# Renesas_Raspi2_Add_On_V1.net
KiCad netlist of a schematic drawn in EAGLE
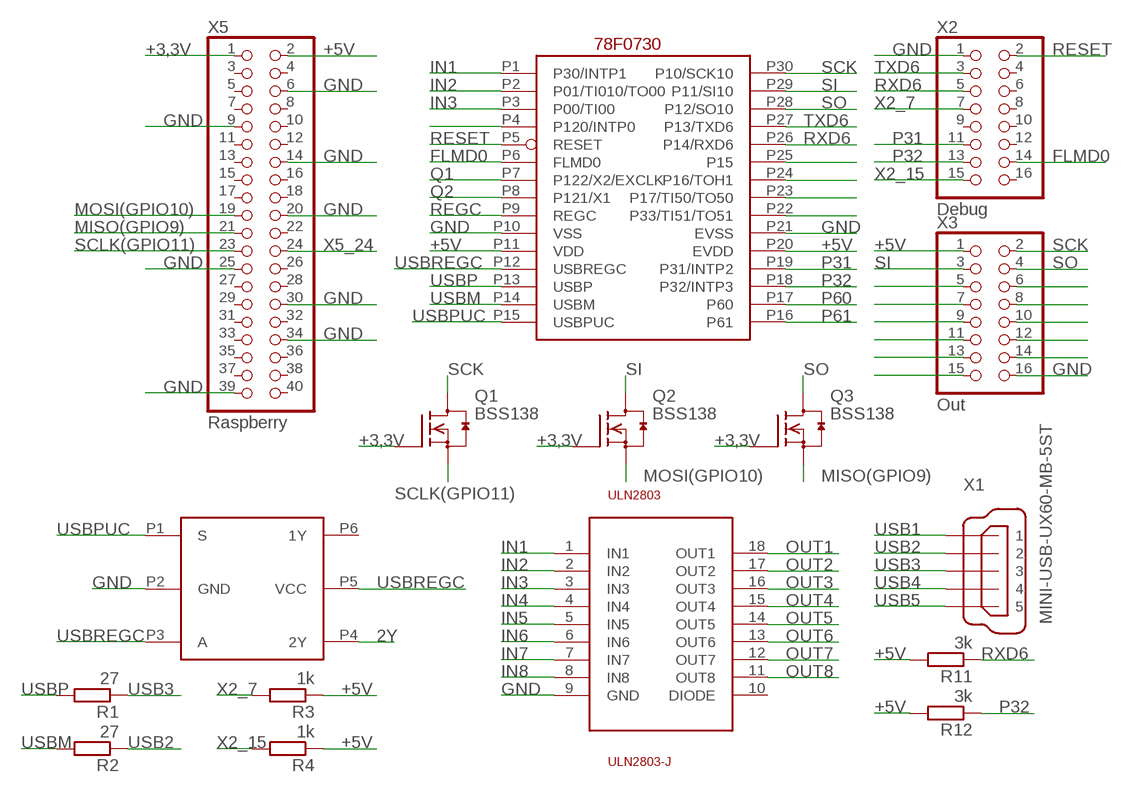
[diagram p0: schematic, sheet 1]
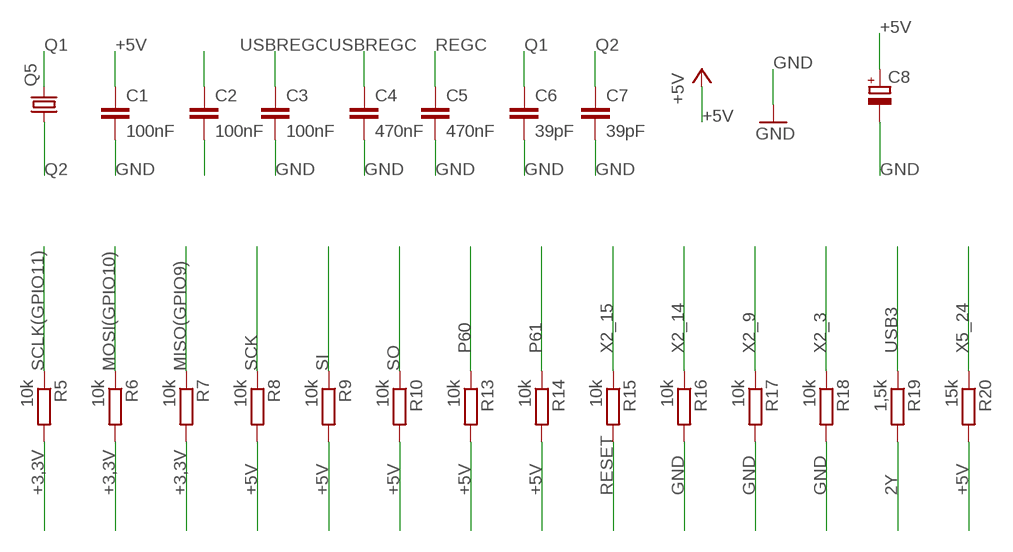
[diagram p1: schematic, sheet 2]

(export (version "E")
  (design (tool "Eeschema 10.0.6"))
  (components
    (comp (ref "Q1")
      (value "BSS138")
      (footprint "eagle-import:SOT23")
      (libsource (lib "eagle-import") (part "BSS138"))
    )
    (comp (ref "Q2")
      (value "BSS138")
      (footprint "eagle-import:SOT23")
      (libsource (lib "eagle-import") (part "BSS138"))
    )
    (comp (ref "Q3")
      (value "BSS138")
      (footprint "eagle-import:SOT23")
      (libsource (lib "eagle-import") (part "BSS138"))
    )
    (comp (ref "R1")
      (value "27")
      (footprint "eagle-import:R0603")
      (libsource (lib "eagle-import") (part "R-EU_R0603"))
    )
    (comp (ref "R2")
      (value "27")
      (footprint "eagle-import:R0603")
      (libsource (lib "eagle-import") (part "R-EU_R0603"))
    )
    (comp (ref "R3")
      (value "1k")
      (footprint "eagle-import:R0603")
      (libsource (lib "eagle-import") (part "R-EU_R0603"))
    )
    (comp (ref "R4")
      (value "1k")
      (footprint "eagle-import:R0603")
      (libsource (lib "eagle-import") (part "R-EU_R0603"))
    )
    (comp (ref "R11")
      (value "3k")
      (footprint "eagle-import:R0603")
      (libsource (lib "eagle-import") (part "R-EU_R0603"))
    )
    (comp (ref "R12")
      (value "3k")
      (footprint "eagle-import:R0603")
      (libsource (lib "eagle-import") (part "R-EU_R0603"))
    )
    (comp (ref "U$1")
      (value "78F0730_CAB_AX")
      (footprint "eagle-import:SSOP30")
      (libsource (lib "eagle-import") (part "78F0730_CAB_AX"))
    )
    (comp (ref "U$2")
      (value "74LVC1G18")
      (footprint "eagle-import:74LVC1G18")
      (libsource (lib "eagle-import") (part "74LVC1G18"))
    )
    (comp (ref "ULN2803")
      (value "ULN2803-J")
      (footprint "eagle-import:SOJ18-45")
      (libsource (lib "eagle-import") (part "ULN2803-J"))
    )
    (comp (ref "X1")
      (value "MINI-USB-UX60-MB-5ST")
      (footprint "eagle-import:UX60-MB-5ST")
      (libsource (lib "eagle-import") (part "MINI-USB-UX60-MB-5ST"))
    )
    (comp (ref "X2")
      (value "Debug")
      (footprint "eagle-import:2X08")
      (libsource (lib "eagle-import") (part "PINHD-2X8"))
    )
    (comp (ref "X3")
      (value "Out")
      (footprint "eagle-import:2X08")
      (libsource (lib "eagle-import") (part "PINHD-2X8"))
    )
    (comp (ref "X5")
      (value "Raspberry")
      (footprint "eagle-import:2X20")
      (libsource (lib "eagle-import") (part "PINHD-2X20"))
    )
    (comp (ref "C1")
      (value "100nF")
      (footprint "eagle-import:C0603")
      (libsource (lib "eagle-import") (part "C-EUC0603"))
    )
    (comp (ref "C2")
      (value "100nF")
      (footprint "eagle-import:C0603")
      (libsource (lib "eagle-import") (part "C-EUC0603"))
    )
    (comp (ref "C3")
      (value "100nF")
      (footprint "eagle-import:C0603")
      (libsource (lib "eagle-import") (part "C-EUC0603"))
    )
    (comp (ref "C4")
      (value "470nF")
      (footprint "eagle-import:C0603")
      (libsource (lib "eagle-import") (part "C-EUC0603"))
    )
    (comp (ref "C5")
      (value "470nF")
      (footprint "eagle-import:C0603")
      (libsource (lib "eagle-import") (part "C-EUC0603"))
    )
    (comp (ref "C6")
      (value "39pF")
      (footprint "eagle-import:C0603")
      (libsource (lib "eagle-import") (part "C-EUC0603"))
    )
    (comp (ref "C7")
      (value "39pF")
      (footprint "eagle-import:C0603")
      (libsource (lib "eagle-import") (part "C-EUC0603"))
    )
    (comp (ref "C8")
      (value "CPOL-EUSANYO_SMD_F8")
      (footprint "eagle-import:SANYO-OSCON_SMD_F8")
      (libsource (lib "eagle-import") (part "CPOL-EUSANYO_SMD_F8"))
    )
    (comp (ref "Q5")
      (value "CRYSTALHC49UP")
      (footprint "eagle-import:HC49UP")
      (libsource (lib "eagle-import") (part "CRYSTALHC49UP"))
    )
    (comp (ref "R5")
      (value "10k")
      (footprint "eagle-import:R0603")
      (libsource (lib "eagle-import") (part "R-EU_R0603"))
    )
    (comp (ref "R6")
      (value "10k")
      (footprint "eagle-import:R0603")
      (libsource (lib "eagle-import") (part "R-EU_R0603"))
    )
    (comp (ref "R7")
      (value "10k")
      (footprint "eagle-import:R0603")
      (libsource (lib "eagle-import") (part "R-EU_R0603"))
    )
    (comp (ref "R8")
      (value "10k")
      (footprint "eagle-import:R0603")
      (libsource (lib "eagle-import") (part "R-EU_R0603"))
    )
    (comp (ref "R9")
      (value "10k")
      (footprint "eagle-import:R0603")
      (libsource (lib "eagle-import") (part "R-EU_R0603"))
    )
    (comp (ref "R10")
      (value "10k")
      (footprint "eagle-import:R0603")
      (libsource (lib "eagle-import") (part "R-EU_R0603"))
    )
    (comp (ref "R13")
      (value "10k")
      (footprint "eagle-import:R0603")
      (libsource (lib "eagle-import") (part "R-EU_R0603"))
    )
    (comp (ref "R14")
      (value "10k")
      (footprint "eagle-import:R0603")
      (libsource (lib "eagle-import") (part "R-EU_R0603"))
    )
    (comp (ref "R15")
      (value "10k")
      (footprint "eagle-import:R0603")
      (libsource (lib "eagle-import") (part "R-EU_R0603"))
    )
    (comp (ref "R16")
      (value "10k")
      (footprint "eagle-import:R0603")
      (libsource (lib "eagle-import") (part "R-EU_R0603"))
    )
    (comp (ref "R17")
      (value "10k")
      (footprint "eagle-import:R0603")
      (libsource (lib "eagle-import") (part "R-EU_R0603"))
    )
    (comp (ref "R18")
      (value "10k")
      (footprint "eagle-import:R0603")
      (libsource (lib "eagle-import") (part "R-EU_R0603"))
    )
    (comp (ref "R19")
      (value "1,5k")
      (footprint "eagle-import:R0603")
      (libsource (lib "eagle-import") (part "R-EU_R0603"))
    )
    (comp (ref "R20")
      (value "15k")
      (footprint "eagle-import:R0603")
      (libsource (lib "eagle-import") (part "R-EU_R0603"))
    )
  )
  (nets
    (net (code "1") (name "+3,3V") (class "Default")
      (node (ref "Q1") (pin "1") (pinfunction "G_1") (pintype "passive"))
      (node (ref "Q2") (pin "1") (pinfunction "G_1") (pintype "passive"))
      (node (ref "Q3") (pin "1") (pinfunction "G_1") (pintype "passive"))
      (node (ref "R5") (pin "2") (pinfunction "2_2") (pintype "passive"))
      (node (ref "R6") (pin "2") (pinfunction "2_2") (pintype "passive"))
      (node (ref "R7") (pin "2") (pinfunction "2_2") (pintype "passive"))
      (node (ref "X5") (pin "1") (pinfunction "1_1") (pintype "passive"))
    )
    (net (code "2") (name "+5V") (class "Default")
      (node (ref "C1") (pin "1") (pinfunction "1_1") (pintype "passive"))
      (node (ref "C8") (pin "+") (pinfunction "+_+") (pintype "passive"))
      (node (ref "R10") (pin "2") (pinfunction "2_2") (pintype "passive"))
      (node (ref "R11") (pin "2") (pinfunction "2_2") (pintype "passive"))
      (node (ref "R12") (pin "2") (pinfunction "2_2") (pintype "passive"))
      (node (ref "R13") (pin "2") (pinfunction "2_2") (pintype "passive"))
      (node (ref "R14") (pin "2") (pinfunction "2_2") (pintype "passive"))
      (node (ref "R20") (pin "2") (pinfunction "2_2") (pintype "passive"))
      (node (ref "R3") (pin "1") (pinfunction "1_1") (pintype "passive"))
      (node (ref "R4") (pin "1") (pinfunction "1_1") (pintype "passive"))
      (node (ref "R8") (pin "2") (pinfunction "2_2") (pintype "passive"))
      (node (ref "R9") (pin "2") (pinfunction "2_2") (pintype "passive"))
      (node (ref "U$1") (pin "P11") (pinfunction "VDD_P11") (pintype "bidirectional"))
      (node (ref "U$1") (pin "P20") (pinfunction "EVDD_P20") (pintype "bidirectional"))
      (node (ref "X3") (pin "1") (pinfunction "1_1") (pintype "passive"))
      (node (ref "X5") (pin "2") (pinfunction "2_2") (pintype "passive"))
    )
    (net (code "3") (name "2Y") (class "Default")
      (node (ref "R19") (pin "2") (pinfunction "2_2") (pintype "passive"))
      (node (ref "U$2") (pin "P4") (pinfunction "2Y_P4") (pintype "bidirectional"))
    )
    (net (code "4") (name "DIODE") (class "Default")
      (node (ref "ULN2803") (pin "10") (pinfunction "DIODE_10") (pintype "power_in"))
    )
    (net (code "5") (name "FLMD0") (class "Default")
      (node (ref "U$1") (pin "P6") (pinfunction "FLMD0_P6") (pintype "bidirectional"))
      (node (ref "X2") (pin "14") (pinfunction "14_14") (pintype "passive"))
    )
    (net (code "6") (name "GND") (class "Default")
      (node (ref "C1") (pin "2") (pinfunction "2_2") (pintype "passive"))
      (node (ref "C3") (pin "2") (pinfunction "2_2") (pintype "passive"))
      (node (ref "C4") (pin "2") (pinfunction "2_2") (pintype "passive"))
      (node (ref "C5") (pin "2") (pinfunction "2_2") (pintype "passive"))
      (node (ref "C6") (pin "2") (pinfunction "2_2") (pintype "passive"))
      (node (ref "C7") (pin "2") (pinfunction "2_2") (pintype "passive"))
      (node (ref "C8") (pin "-") (pinfunction "-_-") (pintype "passive"))
      (node (ref "R16") (pin "2") (pinfunction "2_2") (pintype "passive"))
      (node (ref "R17") (pin "2") (pinfunction "2_2") (pintype "passive"))
      (node (ref "R18") (pin "2") (pinfunction "2_2") (pintype "passive"))
      (node (ref "U$1") (pin "P10") (pinfunction "VSS_P10") (pintype "bidirectional"))
      (node (ref "U$1") (pin "P21") (pinfunction "EVSS_P21") (pintype "bidirectional"))
      (node (ref "U$2") (pin "P2") (pinfunction "GND_P2") (pintype "bidirectional"))
      (node (ref "ULN2803") (pin "9") (pinfunction "GND_9") (pintype "power_in"))
      (node (ref "X2") (pin "1") (pinfunction "1_1") (pintype "passive"))
      (node (ref "X3") (pin "16") (pinfunction "16_16") (pintype "passive"))
      (node (ref "X5") (pin "14") (pinfunction "14_14") (pintype "passive"))
      (node (ref "X5") (pin "20") (pinfunction "20_20") (pintype "passive"))
      (node (ref "X5") (pin "25") (pinfunction "25_25") (pintype "passive"))
      (node (ref "X5") (pin "30") (pinfunction "30_30") (pintype "passive"))
      (node (ref "X5") (pin "34") (pinfunction "34_34") (pintype "passive"))
      (node (ref "X5") (pin "39") (pinfunction "39_39") (pintype "passive"))
      (node (ref "X5") (pin "6") (pinfunction "6_6") (pintype "passive"))
      (node (ref "X5") (pin "9") (pinfunction "9_9") (pintype "passive"))
    )
    (net (code "7") (name "IN1") (class "Default")
      (node (ref "U$1") (pin "P1") (pinfunction "P30/INTP1_P1") (pintype "bidirectional"))
      (node (ref "ULN2803") (pin "1") (pinfunction "IN1_1") (pintype "input"))
    )
    (net (code "8") (name "IN2") (class "Default")
      (node (ref "U$1") (pin "P2") (pinfunction "P01/TI010/TO00_P2") (pintype "bidirectional"))
      (node (ref "ULN2803") (pin "2") (pinfunction "IN2_2") (pintype "input"))
    )
    (net (code "9") (name "IN3") (class "Default")
      (node (ref "U$1") (pin "P3") (pinfunction "P00/TI00_P3") (pintype "bidirectional"))
      (node (ref "ULN2803") (pin "3") (pinfunction "IN3_3") (pintype "input"))
    )
    (net (code "10") (name "IN4") (class "Default")
      (node (ref "ULN2803") (pin "4") (pinfunction "IN4_4") (pintype "input"))
    )
    (net (code "11") (name "IN5") (class "Default")
      (node (ref "ULN2803") (pin "5") (pinfunction "IN5_5") (pintype "input"))
    )
    (net (code "12") (name "IN6") (class "Default")
      (node (ref "ULN2803") (pin "6") (pinfunction "IN6_6") (pintype "input"))
    )
    (net (code "13") (name "IN7") (class "Default")
      (node (ref "ULN2803") (pin "7") (pinfunction "IN7_7") (pintype "input"))
    )
    (net (code "14") (name "IN8") (class "Default")
      (node (ref "ULN2803") (pin "8") (pinfunction "IN8_8") (pintype "input"))
    )
    (net (code "15") (name "MISO(GPIO9)") (class "Default")
      (node (ref "Q3") (pin "2") (pinfunction "S_2") (pintype "passive"))
      (node (ref "R7") (pin "1") (pinfunction "1_1") (pintype "passive"))
      (node (ref "X5") (pin "21") (pinfunction "21_21") (pintype "passive"))
    )
    (net (code "16") (name "MOSI(GPIO10)") (class "Default")
      (node (ref "Q2") (pin "2") (pinfunction "S_2") (pintype "passive"))
      (node (ref "R6") (pin "1") (pinfunction "1_1") (pintype "passive"))
      (node (ref "X5") (pin "19") (pinfunction "19_19") (pintype "passive"))
    )
    (net (code "17") (name "OUT1") (class "Default")
      (node (ref "ULN2803") (pin "18") (pinfunction "OUT1_18") (pintype "open_collector"))
    )
    (net (code "18") (name "OUT2") (class "Default")
      (node (ref "ULN2803") (pin "17") (pinfunction "OUT2_17") (pintype "open_collector"))
    )
    (net (code "19") (name "OUT3") (class "Default")
      (node (ref "ULN2803") (pin "16") (pinfunction "OUT3_16") (pintype "open_collector"))
    )
    (net (code "20") (name "OUT4") (class "Default")
      (node (ref "ULN2803") (pin "15") (pinfunction "OUT4_15") (pintype "open_collector"))
    )
    (net (code "21") (name "OUT5") (class "Default")
      (node (ref "ULN2803") (pin "14") (pinfunction "OUT5_14") (pintype "open_collector"))
    )
    (net (code "22") (name "OUT6") (class "Default")
      (node (ref "ULN2803") (pin "13") (pinfunction "OUT6_13") (pintype "open_collector"))
    )
    (net (code "23") (name "OUT7") (class "Default")
      (node (ref "ULN2803") (pin "12") (pinfunction "OUT7_12") (pintype "open_collector"))
    )
    (net (code "24") (name "OUT8") (class "Default")
      (node (ref "ULN2803") (pin "11") (pinfunction "OUT8_11") (pintype "open_collector"))
    )
    (net (code "25") (name "P31") (class "Default")
      (node (ref "U$1") (pin "P19") (pinfunction "P31/INTP2_P19") (pintype "bidirectional"))
      (node (ref "X2") (pin "11") (pinfunction "11_11") (pintype "passive"))
    )
    (net (code "26") (name "P32") (class "Default")
      (node (ref "R12") (pin "1") (pinfunction "1_1") (pintype "passive"))
      (node (ref "U$1") (pin "P18") (pinfunction "P32/INTP3_P18") (pintype "bidirectional"))
      (node (ref "X2") (pin "13") (pinfunction "13_13") (pintype "passive"))
    )
    (net (code "27") (name "P60") (class "Default")
      (node (ref "R13") (pin "1") (pinfunction "1_1") (pintype "passive"))
      (node (ref "U$1") (pin "P17") (pinfunction "P60_P17") (pintype "bidirectional"))
    )
    (net (code "28") (name "P61") (class "Default")
      (node (ref "R14") (pin "1") (pinfunction "1_1") (pintype "passive"))
      (node (ref "U$1") (pin "P16") (pinfunction "P61_P16") (pintype "bidirectional"))
    )
    (net (code "29") (name "Q1") (class "Default")
      (node (ref "C6") (pin "1") (pinfunction "1_1") (pintype "passive"))
      (node (ref "Q5") (pin "2") (pinfunction "2_2") (pintype "passive"))
      (node (ref "U$1") (pin "P7") (pinfunction "P122/X2/EXCLK_P7") (pintype "bidirectional"))
    )
    (net (code "30") (name "Q2") (class "Default")
      (node (ref "C7") (pin "1") (pinfunction "1_1") (pintype "passive"))
      (node (ref "Q5") (pin "1") (pinfunction "1_1") (pintype "passive"))
      (node (ref "U$1") (pin "P8") (pinfunction "P121/X1_P8") (pintype "bidirectional"))
    )
    (net (code "31") (name "REGC") (class "Default")
      (node (ref "C5") (pin "1") (pinfunction "1_1") (pintype "passive"))
      (node (ref "U$1") (pin "P9") (pinfunction "REGC_P9") (pintype "bidirectional"))
    )
    (net (code "32") (name "RESET") (class "Default")
      (node (ref "R15") (pin "2") (pinfunction "2_2") (pintype "passive"))
      (node (ref "U$1") (pin "P5") (pinfunction "RESET_P5") (pintype "bidirectional"))
      (node (ref "X2") (pin "2") (pinfunction "2_2") (pintype "passive"))
    )
    (net (code "33") (name "RXD6") (class "Default")
      (node (ref "R11") (pin "1") (pinfunction "1_1") (pintype "passive"))
      (node (ref "U$1") (pin "P26") (pinfunction "P14/RXD6_P26") (pintype "bidirectional"))
      (node (ref "X2") (pin "5") (pinfunction "5_5") (pintype "passive"))
    )
    (net (code "34") (name "SCK") (class "Default")
      (node (ref "Q1") (pin "3") (pinfunction "D_3") (pintype "passive"))
      (node (ref "R8") (pin "1") (pinfunction "1_1") (pintype "passive"))
      (node (ref "U$1") (pin "P30") (pinfunction "P10/SCK10_P30") (pintype "bidirectional"))
      (node (ref "X3") (pin "2") (pinfunction "2_2") (pintype "passive"))
    )
    (net (code "35") (name "SCLK(GPIO11)") (class "Default")
      (node (ref "Q1") (pin "2") (pinfunction "S_2") (pintype "passive"))
      (node (ref "R5") (pin "1") (pinfunction "1_1") (pintype "passive"))
      (node (ref "X5") (pin "23") (pinfunction "23_23") (pintype "passive"))
    )
    (net (code "36") (name "SI") (class "Default")
      (node (ref "Q2") (pin "3") (pinfunction "D_3") (pintype "passive"))
      (node (ref "R9") (pin "1") (pinfunction "1_1") (pintype "passive"))
      (node (ref "U$1") (pin "P29") (pinfunction "P11/SI10_P29") (pintype "bidirectional"))
      (node (ref "X3") (pin "3") (pinfunction "3_3") (pintype "passive"))
    )
    (net (code "37") (name "SO") (class "Default")
      (node (ref "Q3") (pin "3") (pinfunction "D_3") (pintype "passive"))
      (node (ref "R10") (pin "1") (pinfunction "1_1") (pintype "passive"))
      (node (ref "U$1") (pin "P28") (pinfunction "P12/SO10_P28") (pintype "bidirectional"))
      (node (ref "X3") (pin "4") (pinfunction "4_4") (pintype "passive"))
    )
    (net (code "38") (name "TXD6") (class "Default")
      (node (ref "U$1") (pin "P27") (pinfunction "P13/TXD6_P27") (pintype "bidirectional"))
      (node (ref "X2") (pin "3") (pinfunction "3_3") (pintype "passive"))
    )
    (net (code "39") (name "USB1") (class "Default")
      (node (ref "X1") (pin "1") (pinfunction "1_1") (pintype "input"))
    )
    (net (code "40") (name "USB2") (class "Default")
      (node (ref "R2") (pin "1") (pinfunction "1_1") (pintype "passive"))
      (node (ref "X1") (pin "2") (pinfunction "2_2") (pintype "input"))
    )
    (net (code "41") (name "USB3") (class "Default")
      (node (ref "R1") (pin "1") (pinfunction "1_1") (pintype "passive"))
      (node (ref "R19") (pin "1") (pinfunction "1_1") (pintype "passive"))
      (node (ref "X1") (pin "3") (pinfunction "3_3") (pintype "input"))
    )
    (net (code "42") (name "USB4") (class "Default")
      (node (ref "X1") (pin "4") (pinfunction "4_4") (pintype "input"))
    )
    (net (code "43") (name "USB5") (class "Default")
      (node (ref "X1") (pin "5") (pinfunction "5_5") (pintype "input"))
    )
    (net (code "44") (name "USBM") (class "Default")
      (node (ref "R2") (pin "2") (pinfunction "2_2") (pintype "passive"))
      (node (ref "U$1") (pin "P14") (pinfunction "USBM_P14") (pintype "bidirectional"))
    )
    (net (code "45") (name "USBP") (class "Default")
      (node (ref "R1") (pin "2") (pinfunction "2_2") (pintype "passive"))
      (node (ref "U$1") (pin "P13") (pinfunction "USBP_P13") (pintype "bidirectional"))
    )
    (net (code "46") (name "USBPUC") (class "Default")
      (node (ref "U$1") (pin "P15") (pinfunction "USBPUC_P15") (pintype "bidirectional"))
      (node (ref "U$2") (pin "P1") (pinfunction "S_P1") (pintype "bidirectional"))
    )
    (net (code "47") (name "USBREGC") (class "Default")
      (node (ref "C3") (pin "1") (pinfunction "1_1") (pintype "passive"))
      (node (ref "C4") (pin "1") (pinfunction "1_1") (pintype "passive"))
      (node (ref "U$1") (pin "P12") (pinfunction "USBREGC_P12") (pintype "bidirectional"))
      (node (ref "U$2") (pin "P3") (pinfunction "A_P3") (pintype "bidirectional"))
      (node (ref "U$2") (pin "P5") (pinfunction "VCC_P5") (pintype "bidirectional"))
    )
    (net (code "48") (name "X2_3") (class "Default")
      (node (ref "R18") (pin "1") (pinfunction "1_1") (pintype "passive"))
    )
    (net (code "49") (name "X2_7") (class "Default")
      (node (ref "R3") (pin "2") (pinfunction "2_2") (pintype "passive"))
      (node (ref "X2") (pin "7") (pinfunction "7_7") (pintype "passive"))
    )
    (net (code "50") (name "X2_9") (class "Default")
      (node (ref "R17") (pin "1") (pinfunction "1_1") (pintype "passive"))
    )
    (net (code "51") (name "X2_14") (class "Default")
      (node (ref "R16") (pin "1") (pinfunction "1_1") (pintype "passive"))
    )
    (net (code "52") (name "X2_15") (class "Default")
      (node (ref "R15") (pin "1") (pinfunction "1_1") (pintype "passive"))
      (node (ref "R4") (pin "2") (pinfunction "2_2") (pintype "passive"))
      (node (ref "X2") (pin "15") (pinfunction "15_15") (pintype "passive"))
    )
    (net (code "53") (name "X5_24") (class "Default")
      (node (ref "R20") (pin "1") (pinfunction "1_1") (pintype "passive"))
      (node (ref "X5") (pin "24") (pinfunction "24_24") (pintype "passive"))
    )
    (net (code "54") (name "unconnected-(C2-Pad1)") (class "Default")
      (node (ref "C2") (pin "1") (pinfunction "1_1") (pintype "passive"))
    )
    (net (code "55") (name "unconnected-(C2-Pad2)") (class "Default")
      (node (ref "C2") (pin "2") (pinfunction "2_2") (pintype "passive"))
    )
    (net (code "56") (name "unconnected-(U$1-P15-PadP25)") (class "Default")
      (node (ref "U$1") (pin "P25") (pinfunction "P15_P25") (pintype "bidirectional"))
    )
    (net (code "57") (name "unconnected-(U$1-P16{slash}TOH1-PadP24)") (class "Default")
      (node (ref "U$1") (pin "P24") (pinfunction "P16/TOH1_P24") (pintype "bidirectional"))
    )
    (net (code "58") (name "unconnected-(U$1-P17{slash}TI50{slash}TO50-PadP23)") (class "Default")
      (node (ref "U$1") (pin "P23") (pinfunction "P17/TI50/TO50_P23") (pintype "bidirectional"))
    )
    (net (code "59") (name "unconnected-(U$1-P33{slash}TI51{slash}TO51-PadP22)") (class "Default")
      (node (ref "U$1") (pin "P22") (pinfunction "P33/TI51/TO51_P22") (pintype "bidirectional"))
    )
    (net (code "60") (name "unconnected-(U$1-P120{slash}INTP0-PadP4)") (class "Default")
      (node (ref "U$1") (pin "P4") (pinfunction "P120/INTP0_P4") (pintype "bidirectional"))
    )
    (net (code "61") (name "unconnected-(U$2-1Y-PadP6)") (class "Default")
      (node (ref "U$2") (pin "P6") (pinfunction "1Y_P6") (pintype "bidirectional"))
    )
    (net (code "62") (name "unconnected-(X2-Pad4)") (class "Default")
      (node (ref "X2") (pin "4") (pinfunction "4_4") (pintype "passive"))
    )
    (net (code "63") (name "unconnected-(X2-Pad6)") (class "Default")
      (node (ref "X2") (pin "6") (pinfunction "6_6") (pintype "passive"))
    )
    (net (code "64") (name "unconnected-(X2-Pad8)") (class "Default")
      (node (ref "X2") (pin "8") (pinfunction "8_8") (pintype "passive"))
    )
    (net (code "65") (name "unconnected-(X2-Pad9)") (class "Default")
      (node (ref "X2") (pin "9") (pinfunction "9_9") (pintype "passive"))
    )
    (net (code "66") (name "unconnected-(X2-Pad10)") (class "Default")
      (node (ref "X2") (pin "10") (pinfunction "10_10") (pintype "passive"))
    )
    (net (code "67") (name "unconnected-(X2-Pad12)") (class "Default")
      (node (ref "X2") (pin "12") (pinfunction "12_12") (pintype "passive"))
    )
    (net (code "68") (name "unconnected-(X2-Pad16)") (class "Default")
      (node (ref "X2") (pin "16") (pinfunction "16_16") (pintype "passive"))
    )
    (net (code "69") (name "unconnected-(X3-Pad5)") (class "Default")
      (node (ref "X3") (pin "5") (pinfunction "5_5") (pintype "passive"))
    )
    (net (code "70") (name "unconnected-(X3-Pad6)") (class "Default")
      (node (ref "X3") (pin "6") (pinfunction "6_6") (pintype "passive"))
    )
    (net (code "71") (name "unconnected-(X3-Pad7)") (class "Default")
      (node (ref "X3") (pin "7") (pinfunction "7_7") (pintype "passive"))
    )
    (net (code "72") (name "unconnected-(X3-Pad8)") (class "Default")
      (node (ref "X3") (pin "8") (pinfunction "8_8") (pintype "passive"))
    )
    (net (code "73") (name "unconnected-(X3-Pad9)") (class "Default")
      (node (ref "X3") (pin "9") (pinfunction "9_9") (pintype "passive"))
    )
    (net (code "74") (name "unconnected-(X3-Pad10)") (class "Default")
      (node (ref "X3") (pin "10") (pinfunction "10_10") (pintype "passive"))
    )
    (net (code "75") (name "unconnected-(X3-Pad11)") (class "Default")
      (node (ref "X3") (pin "11") (pinfunction "11_11") (pintype "passive"))
    )
    (net (code "76") (name "unconnected-(X3-Pad12)") (class "Default")
      (node (ref "X3") (pin "12") (pinfunction "12_12") (pintype "passive"))
    )
    (net (code "77") (name "unconnected-(X3-Pad13)") (class "Default")
      (node (ref "X3") (pin "13") (pinfunction "13_13") (pintype "passive"))
    )
    (net (code "78") (name "unconnected-(X3-Pad14)") (class "Default")
      (node (ref "X3") (pin "14") (pinfunction "14_14") (pintype "passive"))
    )
    (net (code "79") (name "unconnected-(X3-Pad15)") (class "Default")
      (node (ref "X3") (pin "15") (pinfunction "15_15") (pintype "passive"))
    )
    (net (code "80") (name "unconnected-(X5-Pad3)") (class "Default")
      (node (ref "X5") (pin "3") (pinfunction "3_3") (pintype "passive"))
    )
    (net (code "81") (name "unconnected-(X5-Pad4)") (class "Default")
      (node (ref "X5") (pin "4") (pinfunction "4_4") (pintype "passive"))
    )
    (net (code "82") (name "unconnected-(X5-Pad5)") (class "Default")
      (node (ref "X5") (pin "5") (pinfunction "5_5") (pintype "passive"))
    )
    (net (code "83") (name "unconnected-(X5-Pad7)") (class "Default")
      (node (ref "X5") (pin "7") (pinfunction "7_7") (pintype "passive"))
    )
    (net (code "84") (name "unconnected-(X5-Pad8)") (class "Default")
      (node (ref "X5") (pin "8") (pinfunction "8_8") (pintype "passive"))
    )
    (net (code "85") (name "unconnected-(X5-Pad10)") (class "Default")
      (node (ref "X5") (pin "10") (pinfunction "10_10") (pintype "passive"))
    )
    (net (code "86") (name "unconnected-(X5-Pad11)") (class "Default")
      (node (ref "X5") (pin "11") (pinfunction "11_11") (pintype "passive"))
    )
    (net (code "87") (name "unconnected-(X5-Pad12)") (class "Default")
      (node (ref "X5") (pin "12") (pinfunction "12_12") (pintype "passive"))
    )
    (net (code "88") (name "unconnected-(X5-Pad13)") (class "Default")
      (node (ref "X5") (pin "13") (pinfunction "13_13") (pintype "passive"))
    )
    (net (code "89") (name "unconnected-(X5-Pad15)") (class "Default")
      (node (ref "X5") (pin "15") (pinfunction "15_15") (pintype "passive"))
    )
    (net (code "90") (name "unconnected-(X5-Pad16)") (class "Default")
      (node (ref "X5") (pin "16") (pinfunction "16_16") (pintype "passive"))
    )
    (net (code "91") (name "unconnected-(X5-Pad17)") (class "Default")
      (node (ref "X5") (pin "17") (pinfunction "17_17") (pintype "passive"))
    )
    (net (code "92") (name "unconnected-(X5-Pad18)") (class "Default")
      (node (ref "X5") (pin "18") (pinfunction "18_18") (pintype "passive"))
    )
    (net (code "93") (name "unconnected-(X5-Pad22)") (class "Default")
      (node (ref "X5") (pin "22") (pinfunction "22_22") (pintype "passive"))
    )
    (net (code "94") (name "unconnected-(X5-Pad26)") (class "Default")
      (node (ref "X5") (pin "26") (pinfunction "26_26") (pintype "passive"))
    )
    (net (code "95") (name "unconnected-(X5-Pad27)") (class "Default")
      (node (ref "X5") (pin "27") (pinfunction "27_27") (pintype "passive"))
    )
    (net (code "96") (name "unconnected-(X5-Pad28)") (class "Default")
      (node (ref "X5") (pin "28") (pinfunction "28_28") (pintype "passive"))
    )
    (net (code "97") (name "unconnected-(X5-Pad29)") (class "Default")
      (node (ref "X5") (pin "29") (pinfunction "29_29") (pintype "passive"))
    )
    (net (code "98") (name "unconnected-(X5-Pad31)") (class "Default")
      (node (ref "X5") (pin "31") (pinfunction "31_31") (pintype "passive"))
    )
    (net (code "99") (name "unconnected-(X5-Pad32)") (class "Default")
      (node (ref "X5") (pin "32") (pinfunction "32_32") (pintype "passive"))
    )
    (net (code "100") (name "unconnected-(X5-Pad33)") (class "Default")
      (node (ref "X5") (pin "33") (pinfunction "33_33") (pintype "passive"))
    )
    (net (code "101") (name "unconnected-(X5-Pad35)") (class "Default")
      (node (ref "X5") (pin "35") (pinfunction "35_35") (pintype "passive"))
    )
    (net (code "102") (name "unconnected-(X5-Pad36)") (class "Default")
      (node (ref "X5") (pin "36") (pinfunction "36_36") (pintype "passive"))
    )
    (net (code "103") (name "unconnected-(X5-Pad37)") (class "Default")
      (node (ref "X5") (pin "37") (pinfunction "37_37") (pintype "passive"))
    )
    (net (code "104") (name "unconnected-(X5-Pad38)") (class "Default")
      (node (ref "X5") (pin "38") (pinfunction "38_38") (pintype "passive"))
    )
    (net (code "105") (name "unconnected-(X5-Pad40)") (class "Default")
      (node (ref "X5") (pin "40") (pinfunction "40_40") (pintype "passive"))
    )
  )
)
